# PWR612A_SH2.net
KiCad netlist of a schematic drawn in Altium Designer
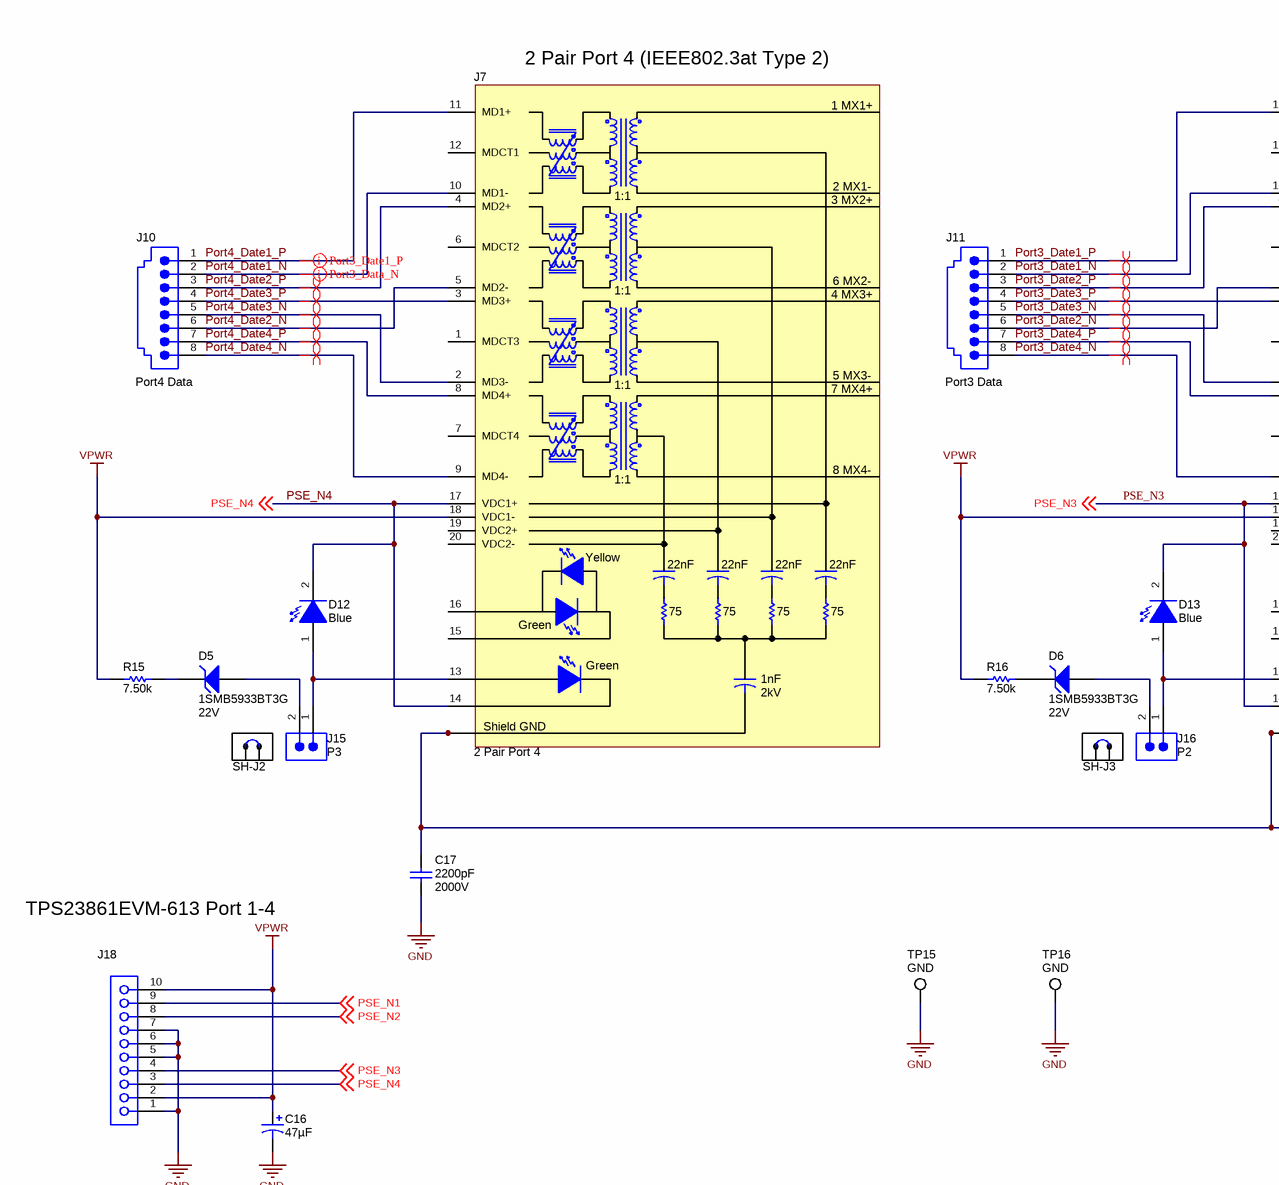
[diagram p0: PWR612A_SH2.SchDoc, top left]
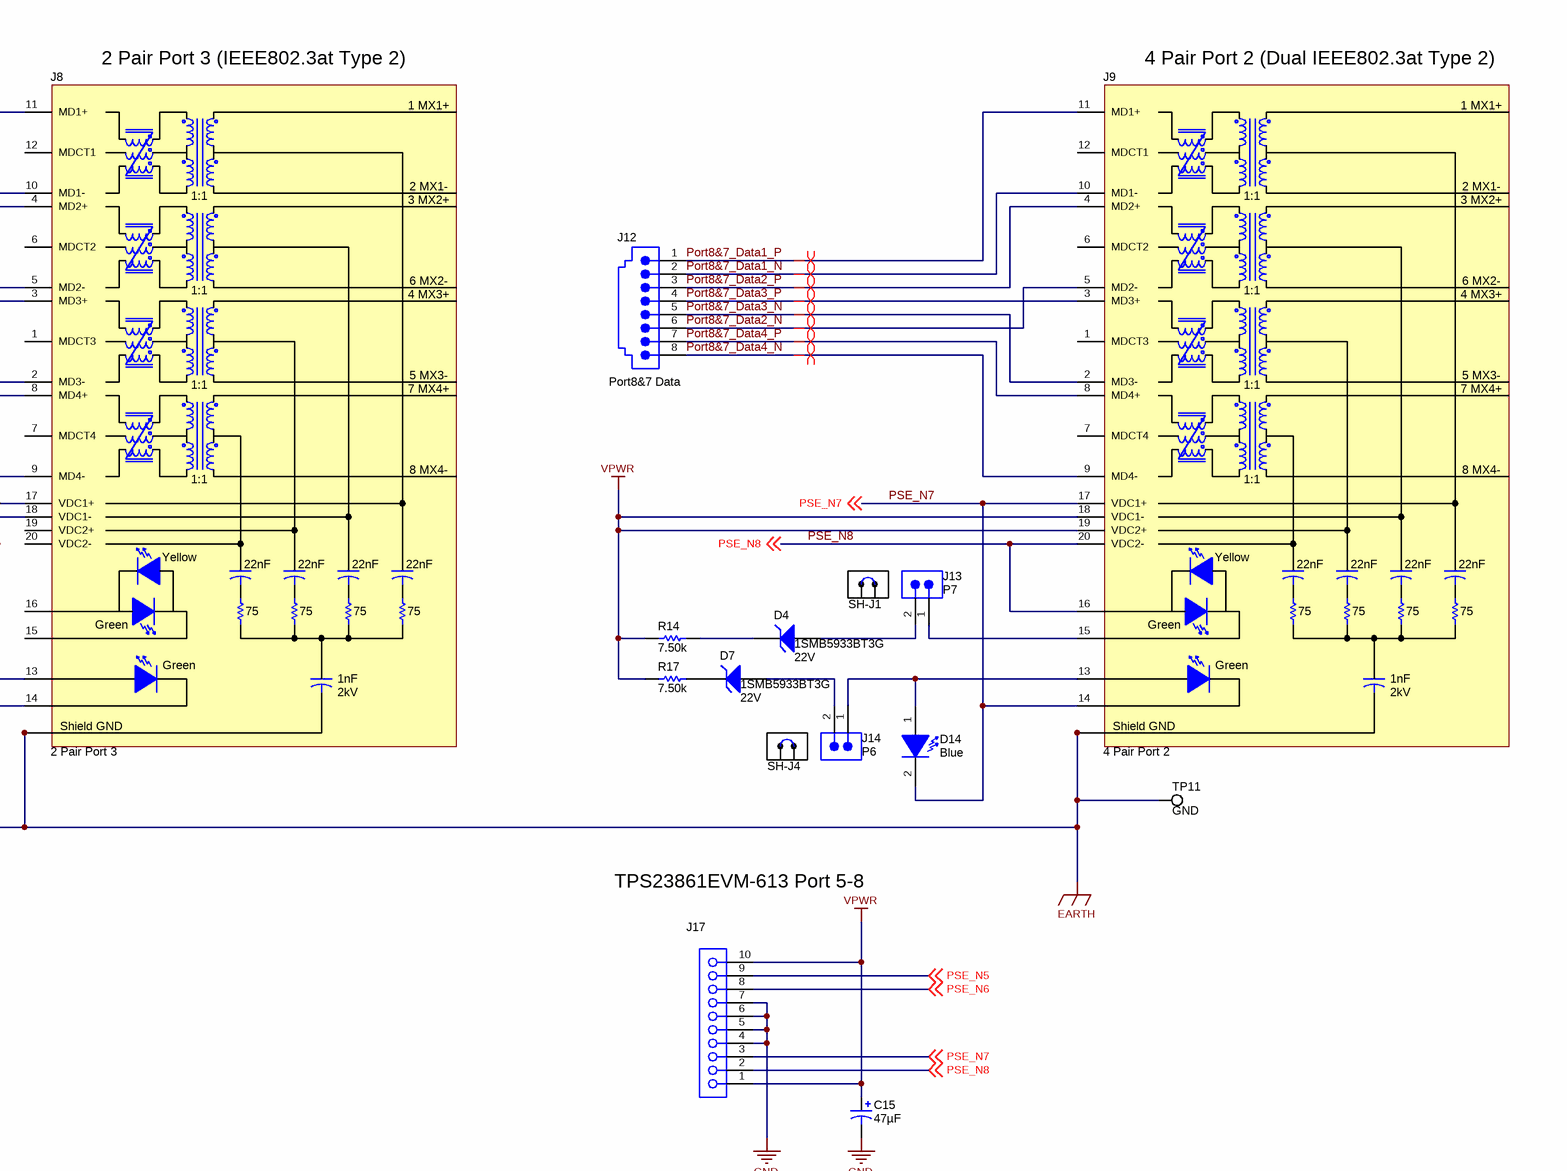
[diagram p1: PWR612A_SH2.SchDoc, top right]
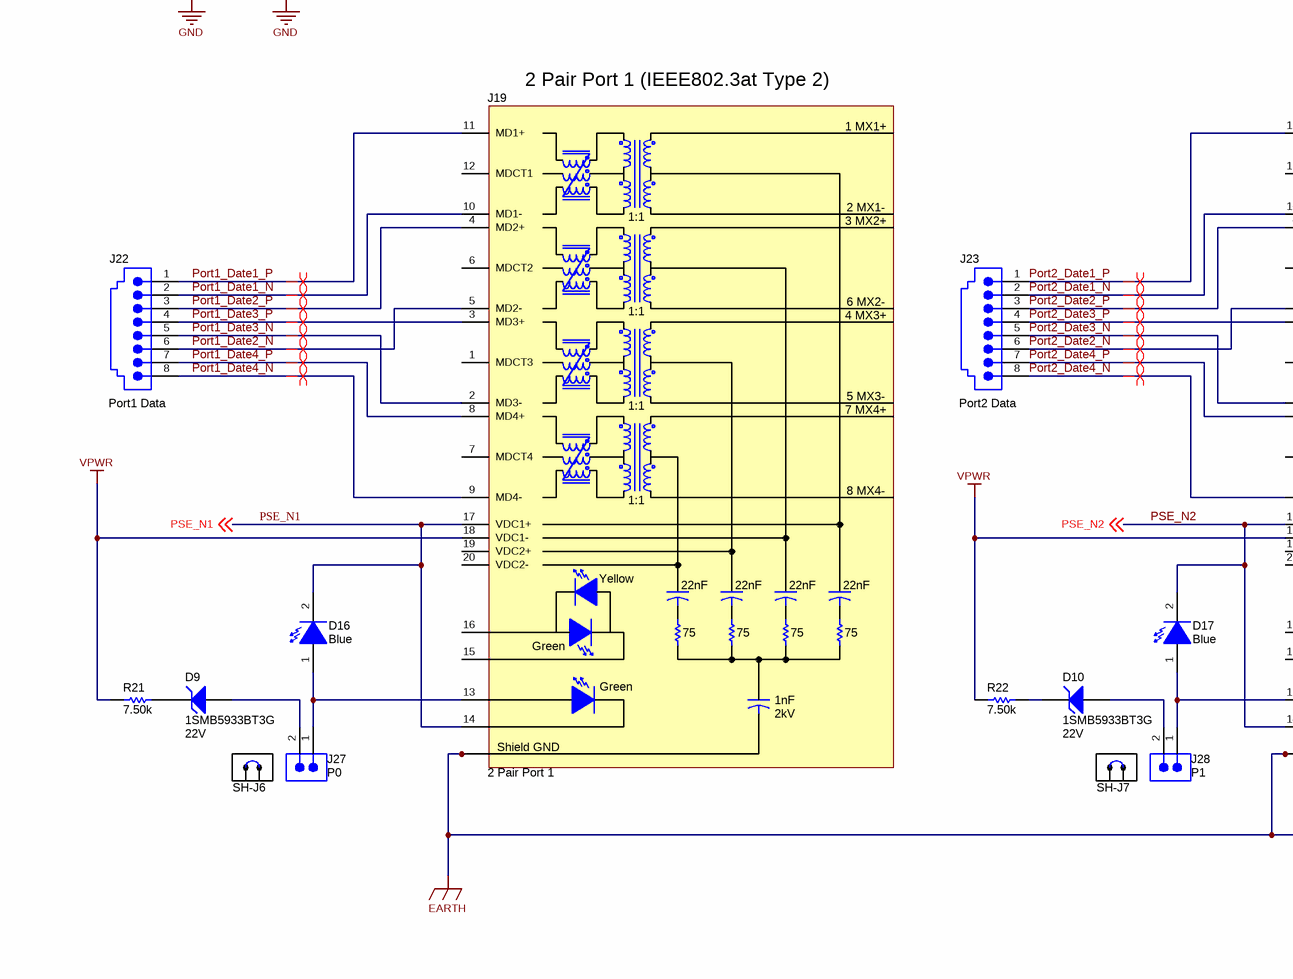
[diagram p2: PWR612A_SH2.SchDoc, bottom left]
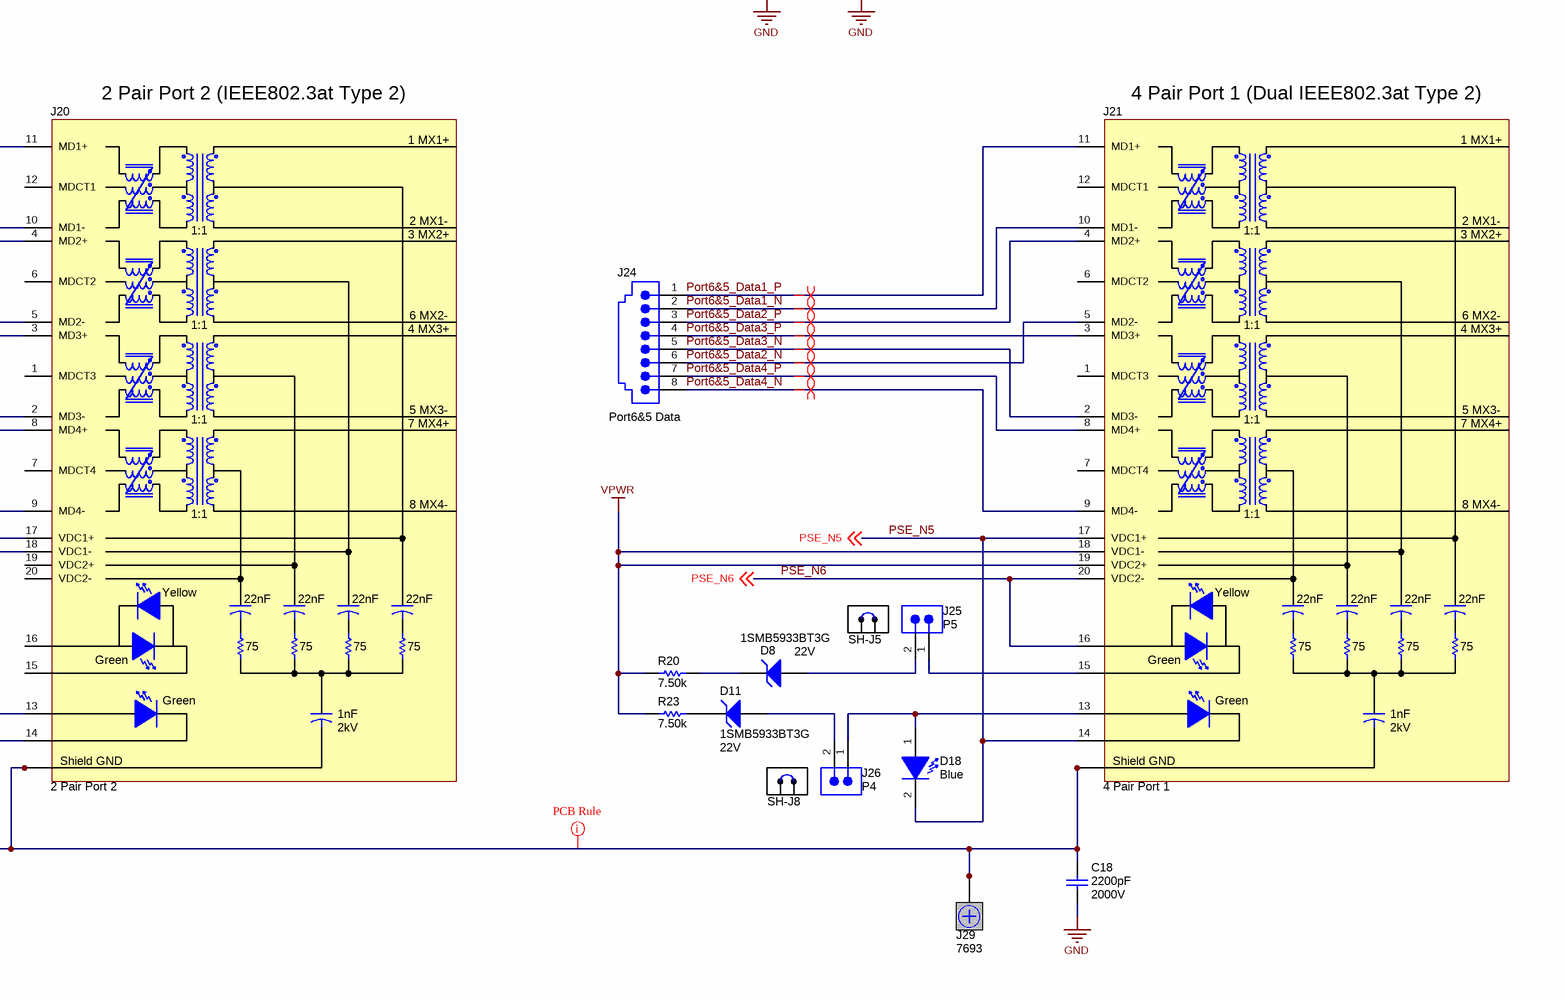
[diagram p3: PWR612A_SH2.SchDoc, bottom right]

(export (version "E")
  (design (tool "Eeschema 10.0.6"))
  (components
    (comp (ref "C15")
      (value "EEV-FK2A470Q")
      (footprint "SM_RADIAL_H13")
      (description "CAP, AL, 47uF, 100V, +/-20%, 0.32 ohm, SMD")
      (fields (field (name "VALUEDISPLAYED") "47µF") (field (name "MANUFACTURER") "Panasonic"))
      (libsource (lib "Capacitor_Aluminum") (part "EEV-FK2A470Q"))
    )
    (comp (ref "C16")
      (value "EEV-FK2A470Q")
      (footprint "SM_RADIAL_H13")
      (description "CAP, AL, 47uF, 100V, +/-20%, 0.32 ohm, SMD")
      (fields (field (name "VALUEDISPLAYED") "47µF") (field (name "MANUFACTURER") "Panasonic"))
      (libsource (lib "Capacitor_Aluminum") (part "EEV-FK2A470Q"))
    )
    (comp (ref "C17")
      (value "C4532X7R3D222K")
      (footprint "1812")
      (description "CAP, CERM, 2200pF, 2000V, +/-10%, X7R, 1812")
      (fields
        (field (name "VALUEDISPLAYED") "2200pF")
        (field (name "MANUFACTURER") "TDK")
        (field (name "VALUE2") "2000V")
      )
      (libsource (lib "Capacitor_Ceramic") (part "C4532X7R3D222K"))
    )
    (comp (ref "C18")
      (value "C4532X7R3D222K")
      (footprint "1812")
      (description "CAP, CERM, 2200pF, 2000V, +/-10%, X7R, 1812")
      (fields
        (field (name "VALUEDISPLAYED") "2200pF")
        (field (name "MANUFACTURER") "TDK")
        (field (name "VALUE2") "2000V")
      )
      (libsource (lib "Capacitor_Ceramic") (part "C4532X7R3D222K"))
    )
    (comp (ref "D4")
      (value "1SMB5933BT3G")
      (footprint "SMB")
      (description "Diode, Zener, 22V, 550mW, SMB")
      (fields (field (name "ALTIUM_VALUE") "22V") (field (name "MANUFACTURER") "ON Semiconductor"))
      (libsource (lib "ZenerDiodes") (part "1SMB5933BT3G"))
    )
    (comp (ref "D5")
      (value "1SMB5933BT3G")
      (footprint "SMB")
      (description "Diode, Zener, 22V, 550mW, SMB")
      (fields (field (name "ALTIUM_VALUE") "22V") (field (name "MANUFACTURER") "ON Semiconductor"))
      (libsource (lib "ZenerDiodes") (part "1SMB5933BT3G"))
    )
    (comp (ref "D6")
      (value "1SMB5933BT3G")
      (footprint "SMB")
      (description "Diode, Zener, 22V, 550mW, SMB")
      (fields (field (name "ALTIUM_VALUE") "22V") (field (name "MANUFACTURER") "ON Semiconductor"))
      (libsource (lib "ZenerDiodes") (part "1SMB5933BT3G"))
    )
    (comp (ref "D7")
      (value "1SMB5933BT3G")
      (footprint "SMB")
      (description "Diode, Zener, 22V, 550mW, SMB")
      (fields (field (name "ALTIUM_VALUE") "22V") (field (name "MANUFACTURER") "ON Semiconductor"))
      (libsource (lib "ZenerDiodes") (part "1SMB5933BT3G"))
    )
    (comp (ref "D8")
      (value "1SMB5933BT3G")
      (footprint "SMB")
      (description "Diode, Zener, 22V, 550mW, SMB")
      (fields (field (name "ALTIUM_VALUE") "22V") (field (name "MANUFACTURER") "ON Semiconductor"))
      (libsource (lib "ZenerDiodes") (part "1SMB5933BT3G"))
    )
    (comp (ref "D9")
      (value "1SMB5933BT3G")
      (footprint "SMB")
      (description "Diode, Zener, 22V, 550mW, SMB")
      (fields (field (name "ALTIUM_VALUE") "22V") (field (name "MANUFACTURER") "ON Semiconductor"))
      (libsource (lib "ZenerDiodes") (part "1SMB5933BT3G"))
    )
    (comp (ref "D10")
      (value "1SMB5933BT3G")
      (footprint "SMB")
      (description "Diode, Zener, 22V, 550mW, SMB")
      (fields (field (name "ALTIUM_VALUE") "22V") (field (name "MANUFACTURER") "ON Semiconductor"))
      (libsource (lib "ZenerDiodes") (part "1SMB5933BT3G"))
    )
    (comp (ref "D11")
      (value "1SMB5933BT3G")
      (footprint "SMB")
      (description "Diode, Zener, 22V, 550mW, SMB")
      (fields (field (name "ALTIUM_VALUE") "22V") (field (name "MANUFACTURER") "ON Semiconductor"))
      (libsource (lib "ZenerDiodes") (part "1SMB5933BT3G"))
    )
    (comp (ref "D12")
      (value "Blue")
      (footprint "LB Q39G_BLUE")
      (description "LED, Blue, SMD")
      (fields (field (name "MANUFACTURER") "OSRAM") (field (name "PARTNUMBER") "LB Q39G-L2N2-35-1"))
      (libsource (lib "LED") (part "LB Q39G-L2N2-35-1"))
    )
    (comp (ref "D13")
      (value "Blue")
      (footprint "LB Q39G_BLUE")
      (description "LED, Blue, SMD")
      (fields (field (name "MANUFACTURER") "OSRAM") (field (name "PARTNUMBER") "LB Q39G-L2N2-35-1"))
      (libsource (lib "LED") (part "LB Q39G-L2N2-35-1"))
    )
    (comp (ref "D14")
      (value "Blue")
      (footprint "LB Q39G_BLUE")
      (description "LED, Blue, SMD")
      (fields (field (name "MANUFACTURER") "OSRAM") (field (name "PARTNUMBER") "LB Q39G-L2N2-35-1"))
      (libsource (lib "LED") (part "LB Q39G-L2N2-35-1"))
    )
    (comp (ref "D16")
      (value "Blue")
      (footprint "LB Q39G_BLUE")
      (description "LED, Blue, SMD")
      (fields (field (name "MANUFACTURER") "OSRAM") (field (name "PARTNUMBER") "LB Q39G-L2N2-35-1"))
      (libsource (lib "LED") (part "LB Q39G-L2N2-35-1"))
    )
    (comp (ref "D17")
      (value "Blue")
      (footprint "LB Q39G_BLUE")
      (description "LED, Blue, SMD")
      (fields (field (name "MANUFACTURER") "OSRAM") (field (name "PARTNUMBER") "LB Q39G-L2N2-35-1"))
      (libsource (lib "LED") (part "LB Q39G-L2N2-35-1"))
    )
    (comp (ref "D18")
      (value "Blue")
      (footprint "LB Q39G_BLUE")
      (description "LED, Blue, SMD")
      (fields (field (name "MANUFACTURER") "OSRAM") (field (name "PARTNUMBER") "LB Q39G-L2N2-35-1"))
      (libsource (lib "LED") (part "LB Q39G-L2N2-35-1"))
    )
    (comp (ref "J7")
      (value "2 Pair Port 4")
      (footprint "JK0-0177NL")
      (description "RJ-45 with integrated magnetics")
      (fields (field (name "MANUFACTURER") "Pulse Engineering") (field (name "PARTNUMBER") "JK0-0177NL"))
      (libsource (lib "Connectors") (part "JK0-0177NL"))
    )
    (comp (ref "J8")
      (value "2 Pair Port 3")
      (footprint "JK0-0177NL")
      (description "RJ-45 with integrated magnetics")
      (fields (field (name "MANUFACTURER") "Pulse Engineering") (field (name "PARTNUMBER") "JK0-0177NL"))
      (libsource (lib "Connectors") (part "JK0-0177NL"))
    )
    (comp (ref "J9")
      (value "4 Pair Port 2")
      (footprint "JK0-0177NL")
      (description "RJ-45 with integrated magnetics")
      (fields (field (name "MANUFACTURER") "Pulse Engineering") (field (name "PARTNUMBER") "JK0-0177NL"))
      (libsource (lib "Connectors") (part "JK0-0177NL"))
    )
    (comp (ref "J10")
      (value "SS-7188V-A-NF")
      (footprint "CONN_SS-7188V-A-NF")
      (description "RJ-45, Vertical, TH")
      (fields (field (name "MANUFACTURER") "Stewart Connector"))
      (libsource (lib "Connectors") (part "SS-7188V-A-NF"))
    )
    (comp (ref "J11")
      (value "SS-7188V-A-NF")
      (footprint "CONN_SS-7188V-A-NF")
      (description "RJ-45, Vertical, TH")
      (fields (field (name "MANUFACTURER") "Stewart Connector"))
      (libsource (lib "Connectors") (part "SS-7188V-A-NF"))
    )
    (comp (ref "J12")
      (value "SS-7188V-A-NF")
      (footprint "CONN_SS-7188V-A-NF")
      (description "RJ-45, Vertical, TH")
      (fields (field (name "MANUFACTURER") "Stewart Connector"))
      (libsource (lib "Connectors") (part "SS-7188V-A-NF"))
    )
    (comp (ref "J13")
      (value "P7")
      (footprint "TSW-102-07-G-S")
      (description "Header, TH, 100mil, 2x1, Gold plated, 230 mil above insulator")
      (fields (field (name "PARTNUMBER") "TSW-102-07-G-S") (field (name "MANUFACTURER") "Samtec, Inc."))
      (libsource (lib "Connectors") (part "TSW-102-07-G-S"))
    )
    (comp (ref "J14")
      (value "P6")
      (footprint "TSW-102-07-G-S")
      (description "Header, TH, 100mil, 2x1, Gold plated, 230 mil above insulator")
      (fields (field (name "PARTNUMBER") "TSW-102-07-G-S") (field (name "MANUFACTURER") "Samtec, Inc."))
      (libsource (lib "") (part "TSW-102-07-G-S_1"))
    )
    (comp (ref "J15")
      (value "P3")
      (footprint "TSW-102-07-G-S")
      (description "Header, TH, 100mil, 2x1, Gold plated, 230 mil above insulator")
      (fields (field (name "PARTNUMBER") "TSW-102-07-G-S") (field (name "MANUFACTURER") "Samtec, Inc."))
      (libsource (lib "") (part "TSW-102-07-G-S_1"))
    )
    (comp (ref "J16")
      (value "P2")
      (footprint "TSW-102-07-G-S")
      (description "Header, TH, 100mil, 2x1, Gold plated, 230 mil above insulator")
      (fields (field (name "PARTNUMBER") "TSW-102-07-G-S") (field (name "MANUFACTURER") "Samtec, Inc."))
      (libsource (lib "") (part "TSW-102-07-G-S_1"))
    )
    (comp (ref "J17")
      (value "Port8&7&6&5")
      (footprint "CONN_SSW-110-23-F-S")
      (description "Connector, Receptacle, 100mil, 10x1, Gold plated, TH")
      (fields (field (name "PARTNUMBER") "SSW-110-01-G-S") (field (name "MANUFACTURER") "Samtec, Inc."))
      (libsource (lib "Connectors") (part "SSW-110-23-F-S"))
    )
    (comp (ref "J18")
      (value "Port4&3&2&1")
      (footprint "CONN_SSW-110-23-F-S")
      (description "Connector, Receptacle, 100mil, 10x1, Gold plated, TH")
      (fields (field (name "PARTNUMBER") "SSW-110-01-G-S") (field (name "MANUFACTURER") "Samtec, Inc."))
      (libsource (lib "Connectors") (part "SSW-110-23-F-S"))
    )
    (comp (ref "J19")
      (value "2 Pair Port 1")
      (footprint "JK0-0177NL")
      (description "RJ-45 with integrated magnetics")
      (fields (field (name "MANUFACTURER") "Pulse Engineering") (field (name "PARTNUMBER") "JK0-0177NL"))
      (libsource (lib "Connectors") (part "JK0-0177NL"))
    )
    (comp (ref "J20")
      (value "2 Pair Port 2")
      (footprint "JK0-0177NL")
      (description "RJ-45 with integrated magnetics")
      (fields (field (name "MANUFACTURER") "Pulse Engineering") (field (name "PARTNUMBER") "JK0-0177NL"))
      (libsource (lib "Connectors") (part "JK0-0177NL"))
    )
    (comp (ref "J21")
      (value "4 Pair Port 1")
      (footprint "JK0-0177NL")
      (description "RJ-45 with integrated magnetics")
      (fields (field (name "MANUFACTURER") "Pulse Engineering") (field (name "PARTNUMBER") "JK0-0177NL"))
      (libsource (lib "Connectors") (part "JK0-0177NL"))
    )
    (comp (ref "J22")
      (value "SS-7188V-A-NF")
      (footprint "CONN_SS-7188V-A-NF")
      (description "RJ-45, Vertical, TH")
      (fields (field (name "MANUFACTURER") "Stewart Connector"))
      (libsource (lib "Connectors") (part "SS-7188V-A-NF"))
    )
    (comp (ref "J23")
      (value "SS-7188V-A-NF")
      (footprint "CONN_SS-7188V-A-NF")
      (description "RJ-45, Vertical, TH")
      (fields (field (name "MANUFACTURER") "Stewart Connector"))
      (libsource (lib "Connectors") (part "SS-7188V-A-NF"))
    )
    (comp (ref "J24")
      (value "SS-7188V-A-NF")
      (footprint "CONN_SS-7188V-A-NF")
      (description "RJ-45, Vertical, TH")
      (fields (field (name "MANUFACTURER") "Stewart Connector"))
      (libsource (lib "Connectors") (part "SS-7188V-A-NF"))
    )
    (comp (ref "J25")
      (value "P5")
      (footprint "TSW-102-07-G-S")
      (description "Header, TH, 100mil, 2x1, Gold plated, 230 mil above insulator")
      (fields (field (name "PARTNUMBER") "TSW-102-07-G-S") (field (name "MANUFACTURER") "Samtec, Inc."))
      (libsource (lib "Connectors") (part "TSW-102-07-G-S"))
    )
    (comp (ref "J26")
      (value "P4")
      (footprint "TSW-102-07-G-S")
      (description "Header, TH, 100mil, 2x1, Gold plated, 230 mil above insulator")
      (fields (field (name "PARTNUMBER") "TSW-102-07-G-S") (field (name "MANUFACTURER") "Samtec, Inc."))
      (libsource (lib "") (part "TSW-102-07-G-S_1"))
    )
    (comp (ref "J27")
      (value "P0")
      (footprint "TSW-102-07-G-S")
      (description "Header, TH, 100mil, 2x1, Gold plated, 230 mil above insulator")
      (fields (field (name "PARTNUMBER") "TSW-102-07-G-S") (field (name "MANUFACTURER") "Samtec, Inc."))
      (libsource (lib "") (part "TSW-102-07-G-S_1"))
    )
    (comp (ref "J28")
      (value "P1")
      (footprint "TSW-102-07-G-S")
      (description "Header, TH, 100mil, 2x1, Gold plated, 230 mil above insulator")
      (fields (field (name "PARTNUMBER") "TSW-102-07-G-S") (field (name "MANUFACTURER") "Samtec, Inc."))
      (libsource (lib "") (part "TSW-102-07-G-S_1"))
    )
    (comp (ref "J29")
      (value "7693")
      (footprint "7693")
      (description "Terminal screw, vertical, snap-in")
      (fields (field (name "MANUFACTURER") "Keystone"))
      (libsource (lib "Connectors") (part "7693"))
    )
    (comp (ref "R14")
      (value "7.50k")
      (footprint "1206")
      (description "RES, 7.50k ohm, 1%, 0.25W, 1206")
      (fields (field (name "PARTNUMBER") "CRCW12067K50FKEA") (field (name "MANUFACTURER") "Vishay-Dale"))
      (libsource (lib "Resistor_1206") (part "CRCW12067K50FKEA"))
    )
    (comp (ref "R15")
      (value "7.50k")
      (footprint "1206")
      (description "RES, 7.50k ohm, 1%, 0.25W, 1206")
      (fields (field (name "PARTNUMBER") "CRCW12067K50FKEA") (field (name "MANUFACTURER") "Vishay-Dale"))
      (libsource (lib "Resistor_1206") (part "CRCW12067K50FKEA"))
    )
    (comp (ref "R16")
      (value "7.50k")
      (footprint "1206")
      (description "RES, 7.50k ohm, 1%, 0.25W, 1206")
      (fields (field (name "PARTNUMBER") "CRCW12067K50FKEA") (field (name "MANUFACTURER") "Vishay-Dale"))
      (libsource (lib "Resistor_1206") (part "CRCW12067K50FKEA"))
    )
    (comp (ref "R17")
      (value "7.50k")
      (footprint "1206")
      (description "RES, 7.50k ohm, 1%, 0.25W, 1206")
      (fields (field (name "PARTNUMBER") "CRCW12067K50FKEA") (field (name "MANUFACTURER") "Vishay-Dale"))
      (libsource (lib "Resistor_1206") (part "CRCW12067K50FKEA"))
    )
    (comp (ref "R20")
      (value "7.50k")
      (footprint "1206")
      (description "RES, 7.50k ohm, 1%, 0.25W, 1206")
      (fields (field (name "PARTNUMBER") "CRCW12067K50FKEA") (field (name "MANUFACTURER") "Vishay-Dale"))
      (libsource (lib "Resistor_1206") (part "CRCW12067K50FKEA"))
    )
    (comp (ref "R21")
      (value "7.50k")
      (footprint "1206")
      (description "RES, 7.50k ohm, 1%, 0.25W, 1206")
      (fields (field (name "PARTNUMBER") "CRCW12067K50FKEA") (field (name "MANUFACTURER") "Vishay-Dale"))
      (libsource (lib "Resistor_1206") (part "CRCW12067K50FKEA"))
    )
    (comp (ref "R22")
      (value "7.50k")
      (footprint "1206")
      (description "RES, 7.50k ohm, 1%, 0.25W, 1206")
      (fields (field (name "PARTNUMBER") "CRCW12067K50FKEA") (field (name "MANUFACTURER") "Vishay-Dale"))
      (libsource (lib "Resistor_1206") (part "CRCW12067K50FKEA"))
    )
    (comp (ref "R23")
      (value "7.50k")
      (footprint "1206")
      (description "RES, 7.50k ohm, 1%, 0.25W, 1206")
      (fields (field (name "PARTNUMBER") "CRCW12067K50FKEA") (field (name "MANUFACTURER") "Vishay-Dale"))
      (libsource (lib "Resistor_1206") (part "CRCW12067K50FKEA"))
    )
    (comp (ref "SH-J1")
      (value "SPC02SYAN")
      (footprint "SPC02SYAN")
      (description "Shunt, 100mil, Flash Gold, Black")
      (fields (field (name "MANUFACTURER") "Sullins Connector Solutions"))
      (libsource (lib "Hardware") (part "SPC02SYAN"))
    )
    (comp (ref "SH-J2")
      (value "SPC02SYAN")
      (footprint "SPC02SYAN")
      (description "Shunt, 100mil, Flash Gold, Black")
      (fields (field (name "MANUFACTURER") "Sullins Connector Solutions"))
      (libsource (lib "Hardware") (part "SPC02SYAN"))
    )
    (comp (ref "SH-J3")
      (value "SPC02SYAN")
      (footprint "SPC02SYAN")
      (description "Shunt, 100mil, Flash Gold, Black")
      (fields (field (name "MANUFACTURER") "Sullins Connector Solutions"))
      (libsource (lib "Hardware") (part "SPC02SYAN"))
    )
    (comp (ref "SH-J4")
      (value "SPC02SYAN")
      (footprint "SPC02SYAN")
      (description "Shunt, 100mil, Flash Gold, Black")
      (fields (field (name "MANUFACTURER") "Sullins Connector Solutions"))
      (libsource (lib "Hardware") (part "SPC02SYAN"))
    )
    (comp (ref "SH-J5")
      (value "SPC02SYAN")
      (footprint "SPC02SYAN")
      (description "Shunt, 100mil, Flash Gold, Black")
      (fields (field (name "MANUFACTURER") "Sullins Connector Solutions"))
      (libsource (lib "Hardware") (part "SPC02SYAN"))
    )
    (comp (ref "SH-J6")
      (value "SPC02SYAN")
      (footprint "SPC02SYAN")
      (description "Shunt, 100mil, Flash Gold, Black")
      (fields (field (name "MANUFACTURER") "Sullins Connector Solutions"))
      (libsource (lib "Hardware") (part "SPC02SYAN"))
    )
    (comp (ref "SH-J7")
      (value "SPC02SYAN")
      (footprint "SPC02SYAN")
      (description "Shunt, 100mil, Flash Gold, Black")
      (fields (field (name "MANUFACTURER") "Sullins Connector Solutions"))
      (libsource (lib "Hardware") (part "SPC02SYAN"))
    )
    (comp (ref "SH-J8")
      (value "SPC02SYAN")
      (footprint "SPC02SYAN")
      (description "Shunt, 100mil, Flash Gold, Black")
      (fields (field (name "MANUFACTURER") "Sullins Connector Solutions"))
      (libsource (lib "Hardware") (part "SPC02SYAN"))
    )
    (comp (ref "TP11")
      (value "GND")
      (footprint "Testpoint_Keystone_Compact")
      (description "Test Point, Compact, SMT")
      (fields (field (name "PARTNUMBER") "5016") (field (name "MANUFACTURER") "Keystone"))
      (libsource (lib "Connectors") (part "5016"))
    )
    (comp (ref "TP15")
      (value "GND")
      (footprint "Testpoint_Keystone_Compact")
      (description "Test Point, Compact, SMT")
      (fields (field (name "PARTNUMBER") "5016") (field (name "MANUFACTURER") "Keystone"))
      (libsource (lib "Connectors") (part "5016"))
    )
    (comp (ref "TP16")
      (value "GND")
      (footprint "Testpoint_Keystone_Compact")
      (description "Test Point, Compact, SMT")
      (fields (field (name "PARTNUMBER") "5016") (field (name "MANUFACTURER") "Keystone"))
      (libsource (lib "Connectors") (part "5016"))
    )
  )
  (nets
    (net (code "1") (name "/Port1_Date1_N") (class "Default")
      (node (ref "J19") (pin "10") (pinfunction "MD1-_10") (pintype "passive"))
      (node (ref "J22") (pin "2") (pinfunction "2_2") (pintype "passive"))
    )
    (net (code "2") (name "/Port1_Date1_P") (class "Default")
      (node (ref "J19") (pin "11") (pinfunction "MD1+_11") (pintype "passive"))
      (node (ref "J22") (pin "1") (pinfunction "1_1") (pintype "passive"))
    )
    (net (code "3") (name "/Port1_Date2_N") (class "Default")
      (node (ref "J19") (pin "5") (pinfunction "MD2-_5") (pintype "passive"))
      (node (ref "J22") (pin "6") (pinfunction "6_6") (pintype "passive"))
    )
    (net (code "4") (name "/Port1_Date2_P") (class "Default")
      (node (ref "J19") (pin "4") (pinfunction "MD2+_4") (pintype "passive"))
      (node (ref "J22") (pin "3") (pinfunction "3_3") (pintype "passive"))
    )
    (net (code "5") (name "/Port1_Date3_N") (class "Default")
      (node (ref "J19") (pin "2") (pinfunction "MD3-_2") (pintype "passive"))
      (node (ref "J22") (pin "5") (pinfunction "5_5") (pintype "passive"))
    )
    (net (code "6") (name "/Port1_Date3_P") (class "Default")
      (node (ref "J19") (pin "3") (pinfunction "MD3+_3") (pintype "passive"))
      (node (ref "J22") (pin "4") (pinfunction "4_4") (pintype "passive"))
    )
    (net (code "7") (name "/Port1_Date4_N") (class "Default")
      (node (ref "J19") (pin "9") (pinfunction "MD4-_9") (pintype "passive"))
      (node (ref "J22") (pin "8") (pinfunction "8_8") (pintype "passive"))
    )
    (net (code "8") (name "/Port1_Date4_P") (class "Default")
      (node (ref "J19") (pin "8") (pinfunction "MD4+_8") (pintype "passive"))
      (node (ref "J22") (pin "7") (pinfunction "7_7") (pintype "passive"))
    )
    (net (code "9") (name "/Port2_Date1_N") (class "Default")
      (node (ref "J20") (pin "10") (pinfunction "MD1-_10") (pintype "passive"))
      (node (ref "J23") (pin "2") (pinfunction "2_2") (pintype "passive"))
    )
    (net (code "10") (name "/Port2_Date1_P") (class "Default")
      (node (ref "J20") (pin "11") (pinfunction "MD1+_11") (pintype "passive"))
      (node (ref "J23") (pin "1") (pinfunction "1_1") (pintype "passive"))
    )
    (net (code "11") (name "/Port2_Date2_N") (class "Default")
      (node (ref "J20") (pin "5") (pinfunction "MD2-_5") (pintype "passive"))
      (node (ref "J23") (pin "6") (pinfunction "6_6") (pintype "passive"))
    )
    (net (code "12") (name "/Port2_Date2_P") (class "Default")
      (node (ref "J20") (pin "4") (pinfunction "MD2+_4") (pintype "passive"))
      (node (ref "J23") (pin "3") (pinfunction "3_3") (pintype "passive"))
    )
    (net (code "13") (name "/Port2_Date3_N") (class "Default")
      (node (ref "J20") (pin "2") (pinfunction "MD3-_2") (pintype "passive"))
      (node (ref "J23") (pin "5") (pinfunction "5_5") (pintype "passive"))
    )
    (net (code "14") (name "/Port2_Date3_P") (class "Default")
      (node (ref "J20") (pin "3") (pinfunction "MD3+_3") (pintype "passive"))
      (node (ref "J23") (pin "4") (pinfunction "4_4") (pintype "passive"))
    )
    (net (code "15") (name "/Port2_Date4_N") (class "Default")
      (node (ref "J20") (pin "9") (pinfunction "MD4-_9") (pintype "passive"))
      (node (ref "J23") (pin "8") (pinfunction "8_8") (pintype "passive"))
    )
    (net (code "16") (name "/Port2_Date4_P") (class "Default")
      (node (ref "J20") (pin "8") (pinfunction "MD4+_8") (pintype "passive"))
      (node (ref "J23") (pin "7") (pinfunction "7_7") (pintype "passive"))
    )
    (net (code "17") (name "/Port3_Date1_N") (class "Default")
      (node (ref "J11") (pin "2") (pinfunction "2_2") (pintype "passive"))
      (node (ref "J8") (pin "10") (pinfunction "MD1-_10") (pintype "passive"))
    )
    (net (code "18") (name "/Port3_Date1_P") (class "Default")
      (node (ref "J11") (pin "1") (pinfunction "1_1") (pintype "passive"))
      (node (ref "J8") (pin "11") (pinfunction "MD1+_11") (pintype "passive"))
    )
    (net (code "19") (name "/Port3_Date2_N") (class "Default")
      (node (ref "J11") (pin "6") (pinfunction "6_6") (pintype "passive"))
      (node (ref "J8") (pin "5") (pinfunction "MD2-_5") (pintype "passive"))
    )
    (net (code "20") (name "/Port3_Date2_P") (class "Default")
      (node (ref "J11") (pin "3") (pinfunction "3_3") (pintype "passive"))
      (node (ref "J8") (pin "4") (pinfunction "MD2+_4") (pintype "passive"))
    )
    (net (code "21") (name "/Port3_Date3_N") (class "Default")
      (node (ref "J11") (pin "5") (pinfunction "5_5") (pintype "passive"))
      (node (ref "J8") (pin "2") (pinfunction "MD3-_2") (pintype "passive"))
    )
    (net (code "22") (name "/Port3_Date3_P") (class "Default")
      (node (ref "J11") (pin "4") (pinfunction "4_4") (pintype "passive"))
      (node (ref "J8") (pin "3") (pinfunction "MD3+_3") (pintype "passive"))
    )
    (net (code "23") (name "/Port3_Date4_N") (class "Default")
      (node (ref "J11") (pin "8") (pinfunction "8_8") (pintype "passive"))
      (node (ref "J8") (pin "9") (pinfunction "MD4-_9") (pintype "passive"))
    )
    (net (code "24") (name "/Port3_Date4_P") (class "Default")
      (node (ref "J11") (pin "7") (pinfunction "7_7") (pintype "passive"))
      (node (ref "J8") (pin "8") (pinfunction "MD4+_8") (pintype "passive"))
    )
    (net (code "25") (name "/Port4_Date1_N") (class "Default")
      (node (ref "J10") (pin "2") (pinfunction "2_2") (pintype "passive"))
      (node (ref "J7") (pin "10") (pinfunction "MD1-_10") (pintype "passive"))
    )
    (net (code "26") (name "/Port4_Date1_P") (class "Default")
      (node (ref "J10") (pin "1") (pinfunction "1_1") (pintype "passive"))
      (node (ref "J7") (pin "11") (pinfunction "MD1+_11") (pintype "passive"))
    )
    (net (code "27") (name "/Port4_Date2_N") (class "Default")
      (node (ref "J10") (pin "6") (pinfunction "6_6") (pintype "passive"))
      (node (ref "J7") (pin "5") (pinfunction "MD2-_5") (pintype "passive"))
    )
    (net (code "28") (name "/Port4_Date2_P") (class "Default")
      (node (ref "J10") (pin "3") (pinfunction "3_3") (pintype "passive"))
      (node (ref "J7") (pin "4") (pinfunction "MD2+_4") (pintype "passive"))
    )
    (net (code "29") (name "/Port4_Date3_N") (class "Default")
      (node (ref "J10") (pin "5") (pinfunction "5_5") (pintype "passive"))
      (node (ref "J7") (pin "2") (pinfunction "MD3-_2") (pintype "passive"))
    )
    (net (code "30") (name "/Port4_Date3_P") (class "Default")
      (node (ref "J10") (pin "4") (pinfunction "4_4") (pintype "passive"))
      (node (ref "J7") (pin "3") (pinfunction "MD3+_3") (pintype "passive"))
    )
    (net (code "31") (name "/Port4_Date4_N") (class "Default")
      (node (ref "J10") (pin "8") (pinfunction "8_8") (pintype "passive"))
      (node (ref "J7") (pin "9") (pinfunction "MD4-_9") (pintype "passive"))
    )
    (net (code "32") (name "/Port4_Date4_P") (class "Default")
      (node (ref "J10") (pin "7") (pinfunction "7_7") (pintype "passive"))
      (node (ref "J7") (pin "8") (pinfunction "MD4+_8") (pintype "passive"))
    )
    (net (code "33") (name "/Port6&5_Data1_N") (class "Default")
      (node (ref "J21") (pin "10") (pinfunction "MD1-_10") (pintype "passive"))
      (node (ref "J24") (pin "2") (pinfunction "2_2") (pintype "passive"))
    )
    (net (code "34") (name "/Port6&5_Data1_P") (class "Default")
      (node (ref "J21") (pin "11") (pinfunction "MD1+_11") (pintype "passive"))
      (node (ref "J24") (pin "1") (pinfunction "1_1") (pintype "passive"))
    )
    (net (code "35") (name "/Port6&5_Data2_N") (class "Default")
      (node (ref "J21") (pin "5") (pinfunction "MD2-_5") (pintype "passive"))
      (node (ref "J24") (pin "6") (pinfunction "6_6") (pintype "passive"))
    )
    (net (code "36") (name "/Port6&5_Data2_P") (class "Default")
      (node (ref "J21") (pin "4") (pinfunction "MD2+_4") (pintype "passive"))
      (node (ref "J24") (pin "3") (pinfunction "3_3") (pintype "passive"))
    )
    (net (code "37") (name "/Port6&5_Data3_N") (class "Default")
      (node (ref "J21") (pin "2") (pinfunction "MD3-_2") (pintype "passive"))
      (node (ref "J24") (pin "5") (pinfunction "5_5") (pintype "passive"))
    )
    (net (code "38") (name "/Port6&5_Data3_P") (class "Default")
      (node (ref "J21") (pin "3") (pinfunction "MD3+_3") (pintype "passive"))
      (node (ref "J24") (pin "4") (pinfunction "4_4") (pintype "passive"))
    )
    (net (code "39") (name "/Port6&5_Data4_N") (class "Default")
      (node (ref "J21") (pin "9") (pinfunction "MD4-_9") (pintype "passive"))
      (node (ref "J24") (pin "8") (pinfunction "8_8") (pintype "passive"))
    )
    (net (code "40") (name "/Port6&5_Data4_P") (class "Default")
      (node (ref "J21") (pin "8") (pinfunction "MD4+_8") (pintype "passive"))
      (node (ref "J24") (pin "7") (pinfunction "7_7") (pintype "passive"))
    )
    (net (code "41") (name "/Port8&7_Data1_N") (class "Default")
      (node (ref "J12") (pin "2") (pinfunction "2_2") (pintype "passive"))
      (node (ref "J9") (pin "10") (pinfunction "MD1-_10") (pintype "passive"))
    )
    (net (code "42") (name "/Port8&7_Data1_P") (class "Default")
      (node (ref "J12") (pin "1") (pinfunction "1_1") (pintype "passive"))
      (node (ref "J9") (pin "11") (pinfunction "MD1+_11") (pintype "passive"))
    )
    (net (code "43") (name "/Port8&7_Data2_N") (class "Default")
      (node (ref "J12") (pin "6") (pinfunction "6_6") (pintype "passive"))
      (node (ref "J9") (pin "5") (pinfunction "MD2-_5") (pintype "passive"))
    )
    (net (code "44") (name "/Port8&7_Data2_P") (class "Default")
      (node (ref "J12") (pin "3") (pinfunction "3_3") (pintype "passive"))
      (node (ref "J9") (pin "4") (pinfunction "MD2+_4") (pintype "passive"))
    )
    (net (code "45") (name "/Port8&7_Data3_N") (class "Default")
      (node (ref "J12") (pin "5") (pinfunction "5_5") (pintype "passive"))
      (node (ref "J9") (pin "2") (pinfunction "MD3-_2") (pintype "passive"))
    )
    (net (code "46") (name "/Port8&7_Data3_P") (class "Default")
      (node (ref "J12") (pin "4") (pinfunction "4_4") (pintype "passive"))
      (node (ref "J9") (pin "3") (pinfunction "MD3+_3") (pintype "passive"))
    )
    (net (code "47") (name "/Port8&7_Data4_N") (class "Default")
      (node (ref "J12") (pin "8") (pinfunction "8_8") (pintype "passive"))
      (node (ref "J9") (pin "9") (pinfunction "MD4-_9") (pintype "passive"))
    )
    (net (code "48") (name "/Port8&7_Data4_P") (class "Default")
      (node (ref "J12") (pin "7") (pinfunction "7_7") (pintype "passive"))
      (node (ref "J9") (pin "8") (pinfunction "MD4+_8") (pintype "passive"))
    )
    (net (code "49") (name "EARTH") (class "Default")
      (node (ref "C17") (pin "1") (pinfunction "1_1") (pintype "passive"))
      (node (ref "C18") (pin "1") (pinfunction "1_1") (pintype "passive"))
      (node (ref "J19") (pin "21") (pinfunction "Shield_21") (pintype "power_in"))
      (node (ref "J19") (pin "22") (pinfunction "Shield_22") (pintype "power_in"))
      (node (ref "J20") (pin "21") (pinfunction "Shield_21") (pintype "power_in"))
      (node (ref "J20") (pin "22") (pinfunction "Shield_22") (pintype "power_in"))
      (node (ref "J21") (pin "21") (pinfunction "Shield_21") (pintype "power_in"))
      (node (ref "J21") (pin "22") (pinfunction "Shield_22") (pintype "power_in"))
      (node (ref "J29") (pin "1") (pinfunction "1_1") (pintype "passive"))
      (node (ref "J29") (pin "2") (pinfunction "2_2") (pintype "passive"))
      (node (ref "J29") (pin "3") (pinfunction "3_3") (pintype "passive"))
      (node (ref "J29") (pin "4") (pinfunction "4_4") (pintype "passive"))
      (node (ref "J7") (pin "21") (pinfunction "Shield_21") (pintype "power_in"))
      (node (ref "J7") (pin "22") (pinfunction "Shield_22") (pintype "power_in"))
      (node (ref "J8") (pin "21") (pinfunction "Shield_21") (pintype "power_in"))
      (node (ref "J8") (pin "22") (pinfunction "Shield_22") (pintype "power_in"))
      (node (ref "J9") (pin "21") (pinfunction "Shield_21") (pintype "power_in"))
      (node (ref "J9") (pin "22") (pinfunction "Shield_22") (pintype "power_in"))
      (node (ref "TP11") (pin "1") (pintype "passive"))
    )
    (net (code "50") (name "GND") (class "Default")
      (node (ref "C15") (pin "2") (pinfunction "-_2") (pintype "passive"))
      (node (ref "C16") (pin "2") (pinfunction "-_2") (pintype "passive"))
      (node (ref "C17") (pin "2") (pinfunction "2_2") (pintype "passive"))
      (node (ref "C18") (pin "2") (pinfunction "2_2") (pintype "passive"))
      (node (ref "J17") (pin "4") (pinfunction "4_4") (pintype "passive"))
      (node (ref "J17") (pin "5") (pinfunction "5_5") (pintype "passive"))
      (node (ref "J17") (pin "6") (pinfunction "6_6") (pintype "passive"))
      (node (ref "J17") (pin "7") (pinfunction "7_7") (pintype "passive"))
      (node (ref "J18") (pin "1") (pinfunction "1_1") (pintype "passive"))
      (node (ref "J18") (pin "5") (pinfunction "5_5") (pintype "passive"))
      (node (ref "J18") (pin "6") (pinfunction "6_6") (pintype "passive"))
      (node (ref "J18") (pin "7") (pinfunction "7_7") (pintype "passive"))
      (node (ref "TP15") (pin "1") (pintype "passive"))
      (node (ref "TP16") (pin "1") (pintype "passive"))
    )
    (net (code "51") (name "Net-(D4-A)") (class "Default")
      (node (ref "D4") (pin "2") (pinfunction "A_2") (pintype "passive"))
      (node (ref "J13") (pin "2") (pinfunction "2_2") (pintype "passive"))
    )
    (net (code "52") (name "Net-(D4-K)") (class "Default")
      (node (ref "D4") (pin "1") (pinfunction "K_1") (pintype "passive"))
      (node (ref "R14") (pin "2") (pinfunction "2_2") (pintype "passive"))
    )
    (net (code "53") (name "Net-(D5-A)") (class "Default")
      (node (ref "D5") (pin "2") (pinfunction "A_2") (pintype "passive"))
      (node (ref "J15") (pin "2") (pinfunction "2_2") (pintype "passive"))
    )
    (net (code "54") (name "Net-(D5-K)") (class "Default")
      (node (ref "D5") (pin "1") (pinfunction "K_1") (pintype "passive"))
      (node (ref "R15") (pin "2") (pinfunction "2_2") (pintype "passive"))
    )
    (net (code "55") (name "Net-(D6-A)") (class "Default")
      (node (ref "D6") (pin "2") (pinfunction "A_2") (pintype "passive"))
      (node (ref "J16") (pin "2") (pinfunction "2_2") (pintype "passive"))
    )
    (net (code "56") (name "Net-(D6-K)") (class "Default")
      (node (ref "D6") (pin "1") (pinfunction "K_1") (pintype "passive"))
      (node (ref "R16") (pin "2") (pinfunction "2_2") (pintype "passive"))
    )
    (net (code "57") (name "Net-(D7-A)") (class "Default")
      (node (ref "D7") (pin "2") (pinfunction "A_2") (pintype "passive"))
      (node (ref "J14") (pin "2") (pinfunction "2_2") (pintype "passive"))
    )
    (net (code "58") (name "Net-(D7-K)") (class "Default")
      (node (ref "D7") (pin "1") (pinfunction "K_1") (pintype "passive"))
      (node (ref "R17") (pin "2") (pinfunction "2_2") (pintype "passive"))
    )
    (net (code "59") (name "Net-(D8-A)") (class "Default")
      (node (ref "D8") (pin "2") (pinfunction "A_2") (pintype "passive"))
      (node (ref "J25") (pin "2") (pinfunction "2_2") (pintype "passive"))
    )
    (net (code "60") (name "Net-(D8-K)") (class "Default")
      (node (ref "D8") (pin "1") (pinfunction "K_1") (pintype "passive"))
      (node (ref "R20") (pin "2") (pinfunction "2_2") (pintype "passive"))
    )
    (net (code "61") (name "Net-(D9-A)") (class "Default")
      (node (ref "D9") (pin "2") (pinfunction "A_2") (pintype "passive"))
      (node (ref "J27") (pin "2") (pinfunction "2_2") (pintype "passive"))
    )
    (net (code "62") (name "Net-(D9-K)") (class "Default")
      (node (ref "D9") (pin "1") (pinfunction "K_1") (pintype "passive"))
      (node (ref "R21") (pin "2") (pinfunction "2_2") (pintype "passive"))
    )
    (net (code "63") (name "Net-(D10-A)") (class "Default")
      (node (ref "D10") (pin "2") (pinfunction "A_2") (pintype "passive"))
      (node (ref "J28") (pin "2") (pinfunction "2_2") (pintype "passive"))
    )
    (net (code "64") (name "Net-(D10-K)") (class "Default")
      (node (ref "D10") (pin "1") (pinfunction "K_1") (pintype "passive"))
      (node (ref "R22") (pin "2") (pinfunction "2_2") (pintype "passive"))
    )
    (net (code "65") (name "Net-(D11-A)") (class "Default")
      (node (ref "D11") (pin "2") (pinfunction "A_2") (pintype "passive"))
      (node (ref "J26") (pin "2") (pinfunction "2_2") (pintype "passive"))
    )
    (net (code "66") (name "Net-(D11-K)") (class "Default")
      (node (ref "D11") (pin "1") (pinfunction "K_1") (pintype "passive"))
      (node (ref "R23") (pin "2") (pinfunction "2_2") (pintype "passive"))
    )
    (net (code "67") (name "Net-(D12-A)") (class "Default")
      (node (ref "D12") (pin "1") (pinfunction "A_1") (pintype "passive"))
      (node (ref "J15") (pin "1") (pinfunction "1_1") (pintype "passive"))
      (node (ref "J7") (pin "13") (pinfunction "13_13") (pintype "passive"))
    )
    (net (code "68") (name "Net-(D13-A)") (class "Default")
      (node (ref "D13") (pin "1") (pinfunction "A_1") (pintype "passive"))
      (node (ref "J16") (pin "1") (pinfunction "1_1") (pintype "passive"))
      (node (ref "J8") (pin "13") (pinfunction "13_13") (pintype "passive"))
    )
    (net (code "69") (name "Net-(D14-A)") (class "Default")
      (node (ref "D14") (pin "1") (pinfunction "A_1") (pintype "passive"))
      (node (ref "J14") (pin "1") (pinfunction "1_1") (pintype "passive"))
      (node (ref "J9") (pin "13") (pinfunction "13_13") (pintype "passive"))
    )
    (net (code "70") (name "Net-(D16-A)") (class "Default")
      (node (ref "D16") (pin "1") (pinfunction "A_1") (pintype "passive"))
      (node (ref "J19") (pin "13") (pinfunction "13_13") (pintype "passive"))
      (node (ref "J27") (pin "1") (pinfunction "1_1") (pintype "passive"))
    )
    (net (code "71") (name "Net-(D17-A)") (class "Default")
      (node (ref "D17") (pin "1") (pinfunction "A_1") (pintype "passive"))
      (node (ref "J20") (pin "13") (pinfunction "13_13") (pintype "passive"))
      (node (ref "J28") (pin "1") (pinfunction "1_1") (pintype "passive"))
    )
    (net (code "72") (name "Net-(D18-A)") (class "Default")
      (node (ref "D18") (pin "1") (pinfunction "A_1") (pintype "passive"))
      (node (ref "J21") (pin "13") (pinfunction "13_13") (pintype "passive"))
      (node (ref "J26") (pin "1") (pinfunction "1_1") (pintype "passive"))
    )
    (net (code "73") (name "Net-(J13-Pad1)") (class "Default")
      (node (ref "J13") (pin "1") (pinfunction "1_1") (pintype "passive"))
      (node (ref "J9") (pin "15") (pinfunction "15_15") (pintype "passive"))
    )
    (net (code "74") (name "Net-(J21-Pad15)") (class "Default")
      (node (ref "J21") (pin "15") (pinfunction "15_15") (pintype "passive"))
      (node (ref "J25") (pin "1") (pinfunction "1_1") (pintype "passive"))
    )
    (net (code "75") (name "PSE_N1") (class "Default")
      (node (ref "D16") (pin "2") (pinfunction "K_2") (pintype "passive"))
      (node (ref "J18") (pin "9") (pinfunction "9_9") (pintype "passive"))
      (node (ref "J19") (pin "14") (pinfunction "14_14") (pintype "passive"))
      (node (ref "J19") (pin "17") (pinfunction "VDC1+_17") (pintype "passive"))
    )
    (net (code "76") (name "PSE_N2") (class "Default")
      (node (ref "D17") (pin "2") (pinfunction "K_2") (pintype "passive"))
      (node (ref "J18") (pin "8") (pinfunction "8_8") (pintype "passive"))
      (node (ref "J20") (pin "14") (pinfunction "14_14") (pintype "passive"))
      (node (ref "J20") (pin "17") (pinfunction "VDC1+_17") (pintype "passive"))
    )
    (net (code "77") (name "PSE_N3") (class "Default")
      (node (ref "D13") (pin "2") (pinfunction "K_2") (pintype "passive"))
      (node (ref "J18") (pin "4") (pinfunction "4_4") (pintype "passive"))
      (node (ref "J8") (pin "14") (pinfunction "14_14") (pintype "passive"))
      (node (ref "J8") (pin "17") (pinfunction "VDC1+_17") (pintype "passive"))
    )
    (net (code "78") (name "PSE_N4") (class "Default")
      (node (ref "D12") (pin "2") (pinfunction "K_2") (pintype "passive"))
      (node (ref "J18") (pin "3") (pinfunction "3_3") (pintype "passive"))
      (node (ref "J7") (pin "14") (pinfunction "14_14") (pintype "passive"))
      (node (ref "J7") (pin "17") (pinfunction "VDC1+_17") (pintype "passive"))
    )
    (net (code "79") (name "PSE_N5") (class "Default")
      (node (ref "D18") (pin "2") (pinfunction "K_2") (pintype "passive"))
      (node (ref "J17") (pin "9") (pinfunction "9_9") (pintype "passive"))
      (node (ref "J21") (pin "14") (pinfunction "14_14") (pintype "passive"))
      (node (ref "J21") (pin "17") (pinfunction "VDC1+_17") (pintype "passive"))
    )
    (net (code "80") (name "PSE_N6") (class "Default")
      (node (ref "J17") (pin "8") (pinfunction "8_8") (pintype "passive"))
      (node (ref "J21") (pin "16") (pinfunction "16_16") (pintype "passive"))
      (node (ref "J21") (pin "20") (pinfunction "VDC2-_20") (pintype "passive"))
    )
    (net (code "81") (name "PSE_N7") (class "Default")
      (node (ref "D14") (pin "2") (pinfunction "K_2") (pintype "passive"))
      (node (ref "J17") (pin "3") (pinfunction "3_3") (pintype "passive"))
      (node (ref "J9") (pin "14") (pinfunction "14_14") (pintype "passive"))
      (node (ref "J9") (pin "17") (pinfunction "VDC1+_17") (pintype "passive"))
    )
    (net (code "82") (name "PSE_N8") (class "Default")
      (node (ref "J17") (pin "2") (pinfunction "2_2") (pintype "passive"))
      (node (ref "J9") (pin "16") (pinfunction "16_16") (pintype "passive"))
      (node (ref "J9") (pin "20") (pinfunction "VDC2-_20") (pintype "passive"))
    )
    (net (code "83") (name "VPWR") (class "Default")
      (node (ref "C15") (pin "1") (pinfunction "+_1") (pintype "passive"))
      (node (ref "C16") (pin "1") (pinfunction "+_1") (pintype "passive"))
      (node (ref "J17") (pin "1") (pinfunction "1_1") (pintype "passive"))
      (node (ref "J17") (pin "10") (pinfunction "10_10") (pintype "passive"))
      (node (ref "J18") (pin "10") (pinfunction "10_10") (pintype "passive"))
      (node (ref "J18") (pin "2") (pinfunction "2_2") (pintype "passive"))
      (node (ref "J19") (pin "18") (pinfunction "VDC1-_18") (pintype "passive"))
      (node (ref "J20") (pin "18") (pinfunction "VDC1-_18") (pintype "passive"))
      (node (ref "J21") (pin "18") (pinfunction "VDC1-_18") (pintype "passive"))
      (node (ref "J21") (pin "19") (pinfunction "VDC2+_19") (pintype "passive"))
      (node (ref "J7") (pin "18") (pinfunction "VDC1-_18") (pintype "passive"))
      (node (ref "J8") (pin "18") (pinfunction "VDC1-_18") (pintype "passive"))
      (node (ref "J9") (pin "18") (pinfunction "VDC1-_18") (pintype "passive"))
      (node (ref "J9") (pin "19") (pinfunction "VDC2+_19") (pintype "passive"))
      (node (ref "R14") (pin "1") (pinfunction "1_1") (pintype "passive"))
      (node (ref "R15") (pin "1") (pinfunction "1_1") (pintype "passive"))
      (node (ref "R16") (pin "1") (pinfunction "1_1") (pintype "passive"))
      (node (ref "R17") (pin "1") (pinfunction "1_1") (pintype "passive"))
      (node (ref "R20") (pin "1") (pinfunction "1_1") (pintype "passive"))
      (node (ref "R21") (pin "1") (pinfunction "1_1") (pintype "passive"))
      (node (ref "R22") (pin "1") (pinfunction "1_1") (pintype "passive"))
      (node (ref "R23") (pin "1") (pinfunction "1_1") (pintype "passive"))
    )
    (net (code "84") (name "unconnected-(J7-MDCT1-Pad12)") (class "Default")
      (node (ref "J7") (pin "12") (pinfunction "MDCT1_12") (pintype "passive"))
    )
    (net (code "85") (name "unconnected-(J7-MDCT2-Pad6)") (class "Default")
      (node (ref "J7") (pin "6") (pinfunction "MDCT2_6") (pintype "passive"))
    )
    (net (code "86") (name "unconnected-(J7-MDCT3-Pad1)") (class "Default")
      (node (ref "J7") (pin "1") (pinfunction "MDCT3_1") (pintype "passive"))
    )
    (net (code "87") (name "unconnected-(J7-MDCT4-Pad7)") (class "Default")
      (node (ref "J7") (pin "7") (pinfunction "MDCT4_7") (pintype "passive"))
    )
    (net (code "88") (name "unconnected-(J7-Pad15)") (class "Default")
      (node (ref "J7") (pin "15") (pinfunction "15_15") (pintype "passive"))
    )
    (net (code "89") (name "unconnected-(J7-Pad16)") (class "Default")
      (node (ref "J7") (pin "16") (pinfunction "16_16") (pintype "passive"))
    )
    (net (code "90") (name "unconnected-(J7-VDC2+-Pad19)") (class "Default")
      (node (ref "J7") (pin "19") (pinfunction "VDC2+_19") (pintype "passive"))
    )
    (net (code "91") (name "unconnected-(J7-VDC2--Pad20)") (class "Default")
      (node (ref "J7") (pin "20") (pinfunction "VDC2-_20") (pintype "passive"))
    )
    (net (code "92") (name "unconnected-(J8-MDCT1-Pad12)") (class "Default")
      (node (ref "J8") (pin "12") (pinfunction "MDCT1_12") (pintype "passive"))
    )
    (net (code "93") (name "unconnected-(J8-MDCT2-Pad6)") (class "Default")
      (node (ref "J8") (pin "6") (pinfunction "MDCT2_6") (pintype "passive"))
    )
    (net (code "94") (name "unconnected-(J8-MDCT3-Pad1)") (class "Default")
      (node (ref "J8") (pin "1") (pinfunction "MDCT3_1") (pintype "passive"))
    )
    (net (code "95") (name "unconnected-(J8-MDCT4-Pad7)") (class "Default")
      (node (ref "J8") (pin "7") (pinfunction "MDCT4_7") (pintype "passive"))
    )
    (net (code "96") (name "unconnected-(J8-Pad15)") (class "Default")
      (node (ref "J8") (pin "15") (pinfunction "15_15") (pintype "passive"))
    )
    (net (code "97") (name "unconnected-(J8-Pad16)") (class "Default")
      (node (ref "J8") (pin "16") (pinfunction "16_16") (pintype "passive"))
    )
    (net (code "98") (name "unconnected-(J8-VDC2+-Pad19)") (class "Default")
      (node (ref "J8") (pin "19") (pinfunction "VDC2+_19") (pintype "passive"))
    )
    (net (code "99") (name "unconnected-(J8-VDC2--Pad20)") (class "Default")
      (node (ref "J8") (pin "20") (pinfunction "VDC2-_20") (pintype "passive"))
    )
    (net (code "100") (name "unconnected-(J9-MDCT1-Pad12)") (class "Default")
      (node (ref "J9") (pin "12") (pinfunction "MDCT1_12") (pintype "passive"))
    )
    (net (code "101") (name "unconnected-(J9-MDCT2-Pad6)") (class "Default")
      (node (ref "J9") (pin "6") (pinfunction "MDCT2_6") (pintype "passive"))
    )
    (net (code "102") (name "unconnected-(J9-MDCT3-Pad1)") (class "Default")
      (node (ref "J9") (pin "1") (pinfunction "MDCT3_1") (pintype "passive"))
    )
    (net (code "103") (name "unconnected-(J9-MDCT4-Pad7)") (class "Default")
      (node (ref "J9") (pin "7") (pinfunction "MDCT4_7") (pintype "passive"))
    )
    (net (code "104") (name "unconnected-(J19-MDCT1-Pad12)") (class "Default")
      (node (ref "J19") (pin "12") (pinfunction "MDCT1_12") (pintype "passive"))
    )
    (net (code "105") (name "unconnected-(J19-MDCT2-Pad6)") (class "Default")
      (node (ref "J19") (pin "6") (pinfunction "MDCT2_6") (pintype "passive"))
    )
    (net (code "106") (name "unconnected-(J19-MDCT3-Pad1)") (class "Default")
      (node (ref "J19") (pin "1") (pinfunction "MDCT3_1") (pintype "passive"))
    )
    (net (code "107") (name "unconnected-(J19-MDCT4-Pad7)") (class "Default")
      (node (ref "J19") (pin "7") (pinfunction "MDCT4_7") (pintype "passive"))
    )
    (net (code "108") (name "unconnected-(J19-Pad15)") (class "Default")
      (node (ref "J19") (pin "15") (pinfunction "15_15") (pintype "passive"))
    )
    (net (code "109") (name "unconnected-(J19-Pad16)") (class "Default")
      (node (ref "J19") (pin "16") (pinfunction "16_16") (pintype "passive"))
    )
    (net (code "110") (name "unconnected-(J19-VDC2+-Pad19)") (class "Default")
      (node (ref "J19") (pin "19") (pinfunction "VDC2+_19") (pintype "passive"))
    )
    (net (code "111") (name "unconnected-(J19-VDC2--Pad20)") (class "Default")
      (node (ref "J19") (pin "20") (pinfunction "VDC2-_20") (pintype "passive"))
    )
    (net (code "112") (name "unconnected-(J20-MDCT1-Pad12)") (class "Default")
      (node (ref "J20") (pin "12") (pinfunction "MDCT1_12") (pintype "passive"))
    )
    (net (code "113") (name "unconnected-(J20-MDCT2-Pad6)") (class "Default")
      (node (ref "J20") (pin "6") (pinfunction "MDCT2_6") (pintype "passive"))
    )
    (net (code "114") (name "unconnected-(J20-MDCT3-Pad1)") (class "Default")
      (node (ref "J20") (pin "1") (pinfunction "MDCT3_1") (pintype "passive"))
    )
    (net (code "115") (name "unconnected-(J20-MDCT4-Pad7)") (class "Default")
      (node (ref "J20") (pin "7") (pinfunction "MDCT4_7") (pintype "passive"))
    )
    (net (code "116") (name "unconnected-(J20-Pad15)") (class "Default")
      (node (ref "J20") (pin "15") (pinfunction "15_15") (pintype "passive"))
    )
    (net (code "117") (name "unconnected-(J20-Pad16)") (class "Default")
      (node (ref "J20") (pin "16") (pinfunction "16_16") (pintype "passive"))
    )
    (net (code "118") (name "unconnected-(J20-VDC2+-Pad19)") (class "Default")
      (node (ref "J20") (pin "19") (pinfunction "VDC2+_19") (pintype "passive"))
    )
    (net (code "119") (name "unconnected-(J20-VDC2--Pad20)") (class "Default")
      (node (ref "J20") (pin "20") (pinfunction "VDC2-_20") (pintype "passive"))
    )
    (net (code "120") (name "unconnected-(J21-MDCT1-Pad12)") (class "Default")
      (node (ref "J21") (pin "12") (pinfunction "MDCT1_12") (pintype "passive"))
    )
    (net (code "121") (name "unconnected-(J21-MDCT2-Pad6)") (class "Default")
      (node (ref "J21") (pin "6") (pinfunction "MDCT2_6") (pintype "passive"))
    )
    (net (code "122") (name "unconnected-(J21-MDCT3-Pad1)") (class "Default")
      (node (ref "J21") (pin "1") (pinfunction "MDCT3_1") (pintype "passive"))
    )
    (net (code "123") (name "unconnected-(J21-MDCT4-Pad7)") (class "Default")
      (node (ref "J21") (pin "7") (pinfunction "MDCT4_7") (pintype "passive"))
    )
  )
)
